# Chronos.net
KiCad netlist of a schematic drawn in EAGLE
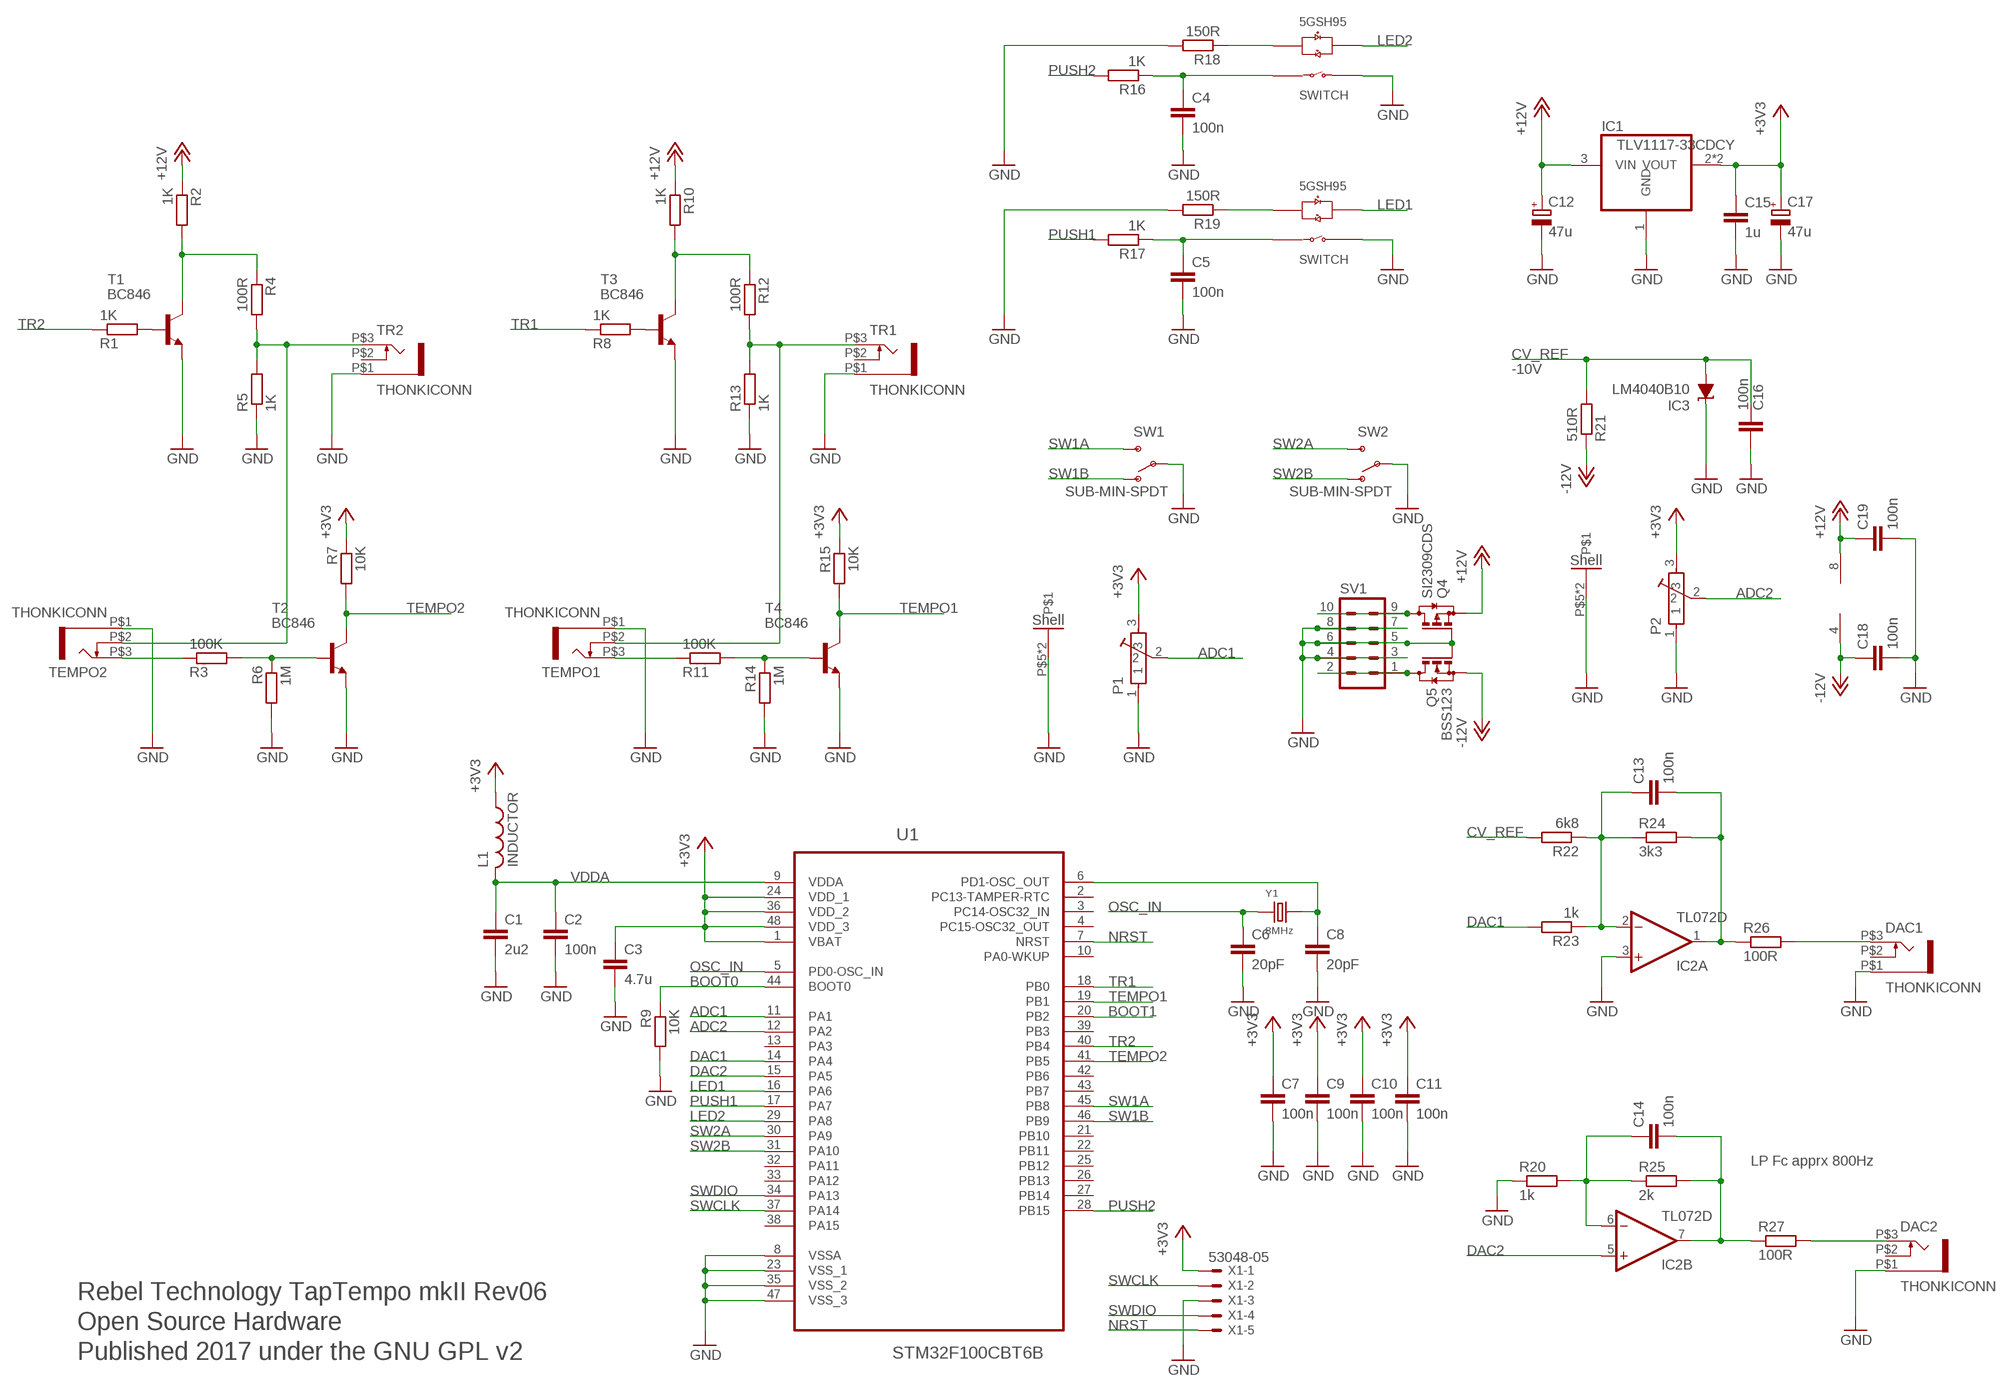
[diagram p0: schematic, sheet 1]

(export (version "E")
  (design (tool "Eeschema 10.0.6"))
  (components
    (comp (ref "C1")
      (value "2u2")
      (footprint "eagle-import:C0603")
      (libsource (lib "eagle-import") (part "C-EUC0603"))
    )
    (comp (ref "C2")
      (value "100n")
      (footprint "eagle-import:C0603")
      (libsource (lib "eagle-import") (part "C-EUC0603"))
    )
    (comp (ref "C3")
      (value "4.7u")
      (footprint "eagle-import:C0603")
      (libsource (lib "eagle-import") (part "C-EUC0603"))
    )
    (comp (ref "C4")
      (value "100n")
      (footprint "eagle-import:C0603")
      (libsource (lib "eagle-import") (part "C-EUC0603"))
    )
    (comp (ref "C5")
      (value "100n")
      (footprint "eagle-import:C0603")
      (libsource (lib "eagle-import") (part "C-EUC0603"))
    )
    (comp (ref "C6")
      (value "20pF")
      (footprint "eagle-import:C0603")
      (libsource (lib "eagle-import") (part "C-EUC0603"))
    )
    (comp (ref "C7")
      (value "100n")
      (footprint "eagle-import:C0603")
      (libsource (lib "eagle-import") (part "C-EUC0603"))
    )
    (comp (ref "C8")
      (value "20pF")
      (footprint "eagle-import:C0603")
      (libsource (lib "eagle-import") (part "C-EUC0603"))
    )
    (comp (ref "C9")
      (value "100n")
      (footprint "eagle-import:C0603")
      (libsource (lib "eagle-import") (part "C-EUC0603"))
    )
    (comp (ref "C10")
      (value "100n")
      (footprint "eagle-import:C0603")
      (libsource (lib "eagle-import") (part "C-EUC0603"))
    )
    (comp (ref "C11")
      (value "100n")
      (footprint "eagle-import:C0603")
      (libsource (lib "eagle-import") (part "C-EUC0603"))
    )
    (comp (ref "C12")
      (value "47u")
      (footprint "eagle-import:CPOL-5")
      (libsource (lib "eagle-import") (part "CPOL-EU153CLV-0505"))
    )
    (comp (ref "C13")
      (value "100n")
      (footprint "eagle-import:C0603")
      (libsource (lib "eagle-import") (part "C-EUC0603"))
    )
    (comp (ref "C14")
      (value "100n")
      (footprint "eagle-import:C0603")
      (libsource (lib "eagle-import") (part "C-EUC0603"))
    )
    (comp (ref "C15")
      (value "1u")
      (footprint "eagle-import:C0603")
      (libsource (lib "eagle-import") (part "C-EUC0603"))
    )
    (comp (ref "C16")
      (value "100n")
      (footprint "eagle-import:C0603")
      (libsource (lib "eagle-import") (part "C-EUC0603"))
    )
    (comp (ref "C17")
      (value "47u")
      (footprint "eagle-import:CPOL-5")
      (libsource (lib "eagle-import") (part "CPOL-EU153CLV-0505"))
    )
    (comp (ref "C18")
      (value "100n")
      (footprint "eagle-import:C0603")
      (libsource (lib "eagle-import") (part "C-EUC0603"))
    )
    (comp (ref "C19")
      (value "100n")
      (footprint "eagle-import:C0603")
      (libsource (lib "eagle-import") (part "C-EUC0603"))
    )
    (comp (ref "DAC1")
      (value "THONKICONN")
      (footprint "eagle-import:THONKICONN")
      (libsource (lib "eagle-import") (part "THONKICONN"))
    )
    (comp (ref "DAC2")
      (value "THONKICONN")
      (footprint "eagle-import:THONKICONN")
      (libsource (lib "eagle-import") (part "THONKICONN"))
    )
    (comp (ref "IC1")
      (value "TLV1117-33CDCY")
      (footprint "eagle-import:SOT223")
      (fields (field (name "MPN") "REG1117"))
      (libsource (lib "eagle-import") (part "REG1117"))
    )
    (comp (ref "IC2")
      (value "TL072D")
      (footprint "eagle-import:SO08")
      (libsource (lib "eagle-import") (part "TL072D"))
    )
    (comp (ref "IC3")
      (value "LM4040B10")
      (footprint "eagle-import:DBZ_R-PDSO-G3")
      (fields (field (name "MF") "TEXAS INSTRUMENT CONNECTORS") (field (name "MPN") "LM4041C12QDBZT"))
      (libsource (lib "eagle-import") (part "LM4041DBZC12"))
    )
    (comp (ref "L1")
      (value "INDUCTOR")
      (footprint "eagle-import:0603")
      (libsource (lib "eagle-import") (part "INDUCTOR"))
    )
    (comp (ref "P1")
      (value "POT-ALPS-RK09L1140")
      (footprint "eagle-import:POT-ALPS-RK09L1140")
      (libsource (lib "eagle-import") (part "POT-ALPS-RK09L1140"))
    )
    (comp (ref "P2")
      (value "POT-ALPS-RK09L1140")
      (footprint "eagle-import:POT-ALPS-RK09L1140")
      (libsource (lib "eagle-import") (part "POT-ALPS-RK09L1140"))
    )
    (comp (ref "PUSH1")
      (value "5GTH9")
      (footprint "eagle-import:5GTH9")
      (libsource (lib "eagle-import") (part "5GTH9"))
    )
    (comp (ref "PUSH2")
      (value "5GTH9")
      (footprint "eagle-import:5GTH9")
      (libsource (lib "eagle-import") (part "5GTH9"))
    )
    (comp (ref "Q4")
      (value "SI2309CDS")
      (footprint "eagle-import:SOT23")
      (libsource (lib "eagle-import") (part "BSS84"))
    )
    (comp (ref "Q5")
      (value "BSS123")
      (footprint "eagle-import:SOT23")
      (libsource (lib "eagle-import") (part "BSS123"))
    )
    (comp (ref "R1")
      (value "1K")
      (footprint "eagle-import:0603")
      (libsource (lib "eagle-import") (part "R-EU_0603"))
    )
    (comp (ref "R2")
      (value "1K")
      (footprint "eagle-import:0603")
      (libsource (lib "eagle-import") (part "R-EU_0603"))
    )
    (comp (ref "R3")
      (value "100K")
      (footprint "eagle-import:0603")
      (libsource (lib "eagle-import") (part "R-EU_0603"))
    )
    (comp (ref "R4")
      (value "100R")
      (footprint "eagle-import:0603")
      (libsource (lib "eagle-import") (part "R-EU_0603"))
    )
    (comp (ref "R5")
      (value "1K")
      (footprint "eagle-import:0603")
      (libsource (lib "eagle-import") (part "R-EU_0603"))
    )
    (comp (ref "R6")
      (value "1M")
      (footprint "eagle-import:0603")
      (libsource (lib "eagle-import") (part "R-EU_0603"))
    )
    (comp (ref "R7")
      (value "10K")
      (footprint "eagle-import:0603")
      (libsource (lib "eagle-import") (part "R-EU_0603"))
    )
    (comp (ref "R8")
      (value "1K")
      (footprint "eagle-import:0603")
      (libsource (lib "eagle-import") (part "R-EU_0603"))
    )
    (comp (ref "R9")
      (value "10K")
      (footprint "eagle-import:0603")
      (libsource (lib "eagle-import") (part "R-EU_0603"))
    )
    (comp (ref "R10")
      (value "1K")
      (footprint "eagle-import:0603")
      (libsource (lib "eagle-import") (part "R-EU_0603"))
    )
    (comp (ref "R11")
      (value "100K")
      (footprint "eagle-import:0603")
      (libsource (lib "eagle-import") (part "R-EU_0603"))
    )
    (comp (ref "R12")
      (value "100R")
      (footprint "eagle-import:0603")
      (libsource (lib "eagle-import") (part "R-EU_0603"))
    )
    (comp (ref "R13")
      (value "1K")
      (footprint "eagle-import:0603")
      (libsource (lib "eagle-import") (part "R-EU_0603"))
    )
    (comp (ref "R14")
      (value "1M")
      (footprint "eagle-import:0603")
      (libsource (lib "eagle-import") (part "R-EU_0603"))
    )
    (comp (ref "R15")
      (value "10K")
      (footprint "eagle-import:0603")
      (libsource (lib "eagle-import") (part "R-EU_0603"))
    )
    (comp (ref "R16")
      (value "1K")
      (footprint "eagle-import:0603")
      (libsource (lib "eagle-import") (part "R-EU_0603"))
    )
    (comp (ref "R17")
      (value "1K")
      (footprint "eagle-import:0603")
      (libsource (lib "eagle-import") (part "R-EU_0603"))
    )
    (comp (ref "R18")
      (value "150R")
      (footprint "eagle-import:0603")
      (libsource (lib "eagle-import") (part "R-EU_0603"))
    )
    (comp (ref "R19")
      (value "150R")
      (footprint "eagle-import:0603")
      (libsource (lib "eagle-import") (part "R-EU_0603"))
    )
    (comp (ref "R20")
      (value "1k")
      (footprint "eagle-import:0603")
      (libsource (lib "eagle-import") (part "R-EU_0603"))
    )
    (comp (ref "R21")
      (value "510R")
      (footprint "eagle-import:0603")
      (libsource (lib "eagle-import") (part "R-EU_0603"))
    )
    (comp (ref "R22")
      (value "6k8")
      (footprint "eagle-import:0603")
      (libsource (lib "eagle-import") (part "R-EU_0603"))
    )
    (comp (ref "R23")
      (value "1k")
      (footprint "eagle-import:0603")
      (libsource (lib "eagle-import") (part "R-EU_0603"))
    )
    (comp (ref "R24")
      (value "3k3")
      (footprint "eagle-import:0603")
      (libsource (lib "eagle-import") (part "R-EU_0603"))
    )
    (comp (ref "R25")
      (value "2k")
      (footprint "eagle-import:0603")
      (libsource (lib "eagle-import") (part "R-EU_0603"))
    )
    (comp (ref "R26")
      (value "100R")
      (footprint "eagle-import:0603")
      (libsource (lib "eagle-import") (part "R-EU_0603"))
    )
    (comp (ref "R27")
      (value "100R")
      (footprint "eagle-import:0603")
      (libsource (lib "eagle-import") (part "R-EU_0603"))
    )
    (comp (ref "SV1")
      (value "MA05-2")
      (footprint "eagle-import:MA05-2")
      (libsource (lib "eagle-import") (part "MA05-2"))
    )
    (comp (ref "SW1")
      (value "SUB-MIN-SPDT")
      (footprint "eagle-import:SUB-MIN-SPDT")
      (libsource (lib "eagle-import") (part "SUB-MIN-SPDT"))
    )
    (comp (ref "SW2")
      (value "SUB-MIN-SPDT")
      (footprint "eagle-import:SUB-MIN-SPDT")
      (libsource (lib "eagle-import") (part "SUB-MIN-SPDT"))
    )
    (comp (ref "T1")
      (value "BC846")
      (footprint "eagle-import:SOT23")
      (libsource (lib "eagle-import") (part "BC846"))
    )
    (comp (ref "T2")
      (value "BC846")
      (footprint "eagle-import:SOT23")
      (libsource (lib "eagle-import") (part "BC846"))
    )
    (comp (ref "T3")
      (value "BC846")
      (footprint "eagle-import:SOT23")
      (libsource (lib "eagle-import") (part "BC846"))
    )
    (comp (ref "T4")
      (value "BC846")
      (footprint "eagle-import:SOT23")
      (libsource (lib "eagle-import") (part "BC846"))
    )
    (comp (ref "TEMPO1")
      (value "THONKICONN")
      (footprint "eagle-import:THONKICONN")
      (libsource (lib "eagle-import") (part "THONKICONN"))
    )
    (comp (ref "TEMPO2")
      (value "THONKICONN")
      (footprint "eagle-import:THONKICONN")
      (libsource (lib "eagle-import") (part "THONKICONN"))
    )
    (comp (ref "TR1")
      (value "THONKICONN")
      (footprint "eagle-import:THONKICONN")
      (libsource (lib "eagle-import") (part "THONKICONN"))
    )
    (comp (ref "TR2")
      (value "THONKICONN")
      (footprint "eagle-import:THONKICONN")
      (libsource (lib "eagle-import") (part "THONKICONN"))
    )
    (comp (ref "U1")
      (value "STM32F100CBT6B")
      (footprint "eagle-import:QFP50P900X900X160-48N")
      (libsource (lib "eagle-import") (part "STM32F100CBT6B"))
    )
    (comp (ref "X1")
      (value "53048-05")
      (footprint "eagle-import:53048-05")
      (fields (field (name "MF") "MOLEX") (field (name "MPN") "53048-0510"))
      (libsource (lib "eagle-import") (part "53?-05048"))
    )
    (comp (ref "Y1")
      (value "8MHz")
      (footprint "eagle-import:X2-SMD-5.0X3.2X1.3MM")
      (fields (field (name "MPN") "5032/2P"))
      (libsource (lib "eagle-import") (part "SMD-CRYSTAL-8MHZ-20PF-20PPM(2P-5.0X3.2MM)"))
    )
  )
  (nets
    (net (code "1") (name "+3V3") (class "Default")
      (node (ref "C10") (pin "1") (pinfunction "1_1") (pintype "passive"))
      (node (ref "C11") (pin "1") (pinfunction "1_1") (pintype "passive"))
      (node (ref "C15") (pin "1") (pinfunction "1_1") (pintype "passive"))
      (node (ref "C17") (pin "+") (pinfunction "+_+") (pintype "passive"))
      (node (ref "C3") (pin "1") (pinfunction "1_1") (pintype "passive"))
      (node (ref "C7") (pin "1") (pinfunction "1_1") (pintype "passive"))
      (node (ref "C9") (pin "1") (pinfunction "1_1") (pintype "passive"))
      (node (ref "IC1") (pin "2") (pinfunction "VOUT_2") (pintype "output"))
      (node (ref "IC1") (pin "4") (pinfunction "VOUT_4") (pintype "output"))
      (node (ref "L1") (pin "1") (pinfunction "1_1") (pintype "passive"))
      (node (ref "P1") (pin "3") (pinfunction "3_3") (pintype "bidirectional"))
      (node (ref "P2") (pin "3") (pinfunction "3_3") (pintype "bidirectional"))
      (node (ref "R15") (pin "1") (pinfunction "1_1") (pintype "passive"))
      (node (ref "R7") (pin "1") (pinfunction "1_1") (pintype "passive"))
      (node (ref "U1") (pin "1") (pinfunction "VBAT_1") (pintype "power_in"))
      (node (ref "U1") (pin "24") (pinfunction "VDD_1_24") (pintype "power_in"))
      (node (ref "U1") (pin "36") (pinfunction "VDD_2_36") (pintype "power_in"))
      (node (ref "U1") (pin "48") (pinfunction "VDD_3_48") (pintype "power_in"))
      (node (ref "X1") (pin "1") (pinfunction "S_1") (pintype "passive"))
    )
    (net (code "2") (name "+12V") (class "Default")
      (node (ref "C12") (pin "+") (pinfunction "+_+") (pintype "passive"))
      (node (ref "C19") (pin "1") (pinfunction "1_1") (pintype "passive"))
      (node (ref "IC1") (pin "3") (pinfunction "VIN_3") (pintype "input"))
      (node (ref "IC2") (pin "8") (pinfunction "V+_8") (pintype "power_in"))
      (node (ref "Q4") (pin "2") (pinfunction "S_2") (pintype "passive"))
      (node (ref "R10") (pin "1") (pinfunction "1_1") (pintype "passive"))
      (node (ref "R2") (pin "1") (pinfunction "1_1") (pintype "passive"))
    )
    (net (code "3") (name "-12V") (class "Default")
      (node (ref "C18") (pin "1") (pinfunction "1_1") (pintype "passive"))
      (node (ref "IC2") (pin "4") (pinfunction "V-_4") (pintype "power_in"))
      (node (ref "Q5") (pin "2") (pinfunction "S_2") (pintype "passive"))
      (node (ref "R21") (pin "1") (pinfunction "1_1") (pintype "passive"))
    )
    (net (code "4") (name "/ADC1") (class "Default")
      (node (ref "P1") (pin "2") (pinfunction "2_2") (pintype "bidirectional"))
      (node (ref "U1") (pin "11") (pinfunction "PA1_11") (pintype "bidirectional"))
    )
    (net (code "5") (name "/ADC2") (class "Default")
      (node (ref "P2") (pin "2") (pinfunction "2_2") (pintype "bidirectional"))
      (node (ref "U1") (pin "12") (pinfunction "PA2_12") (pintype "bidirectional"))
    )
    (net (code "6") (name "/BOOT0") (class "Default")
      (node (ref "R9") (pin "1") (pinfunction "1_1") (pintype "passive"))
      (node (ref "U1") (pin "44") (pinfunction "BOOT0_44") (pintype "input"))
    )
    (net (code "7") (name "/BOOT1") (class "Default")
      (node (ref "U1") (pin "20") (pinfunction "PB2_20") (pintype "bidirectional"))
    )
    (net (code "8") (name "/CV_REF") (class "Default")
      (node (ref "C16") (pin "1") (pinfunction "1_1") (pintype "passive"))
      (node (ref "IC3") (pin "2") (pinfunction "A_2") (pintype "passive"))
      (node (ref "R21") (pin "2") (pinfunction "2_2") (pintype "passive"))
      (node (ref "R22") (pin "2") (pinfunction "2_2") (pintype "passive"))
    )
    (net (code "9") (name "/DAC1") (class "Default")
      (node (ref "R23") (pin "2") (pinfunction "2_2") (pintype "passive"))
      (node (ref "U1") (pin "14") (pinfunction "PA4_14") (pintype "bidirectional"))
    )
    (net (code "10") (name "/DAC2") (class "Default")
      (node (ref "IC2") (pin "5") (pinfunction "+IN_5") (pintype "input"))
      (node (ref "U1") (pin "15") (pinfunction "PA5_15") (pintype "bidirectional"))
    )
    (net (code "11") (name "/LED1") (class "Default")
      (node (ref "PUSH1") (pin "+3") (pinfunction "LED_R+_+3") (pintype "bidirectional"))
      (node (ref "U1") (pin "16") (pinfunction "PA6_16") (pintype "bidirectional"))
    )
    (net (code "12") (name "/LED2") (class "Default")
      (node (ref "PUSH2") (pin "+3") (pinfunction "LED_R+_+3") (pintype "bidirectional"))
      (node (ref "U1") (pin "29") (pinfunction "PA8_29") (pintype "bidirectional"))
    )
    (net (code "13") (name "/NRST") (class "Default")
      (node (ref "U1") (pin "7") (pinfunction "NRST_7") (pintype "bidirectional"))
      (node (ref "X1") (pin "5") (pinfunction "S_5") (pintype "passive"))
    )
    (net (code "14") (name "/OSC_IN") (class "Default")
      (node (ref "C6") (pin "1") (pinfunction "1_1") (pintype "passive"))
      (node (ref "U1") (pin "5") (pinfunction "PD0-OSC_IN_5") (pintype "input"))
      (node (ref "Y1") (pin "1") (pinfunction "1_1") (pintype "passive"))
    )
    (net (code "15") (name "/PUSH1") (class "Default")
      (node (ref "R17") (pin "2") (pinfunction "2_2") (pintype "passive"))
      (node (ref "U1") (pin "17") (pinfunction "PA7_17") (pintype "bidirectional"))
    )
    (net (code "16") (name "/PUSH2") (class "Default")
      (node (ref "R16") (pin "2") (pinfunction "2_2") (pintype "passive"))
      (node (ref "U1") (pin "28") (pinfunction "PB15_28") (pintype "bidirectional"))
    )
    (net (code "17") (name "/SW1A") (class "Default")
      (node (ref "SW1") (pin "3") (pinfunction "S_3") (pintype "passive"))
      (node (ref "U1") (pin "45") (pinfunction "PB8_45") (pintype "bidirectional"))
    )
    (net (code "18") (name "/SW1B") (class "Default")
      (node (ref "SW1") (pin "1") (pinfunction "O_1") (pintype "passive"))
      (node (ref "U1") (pin "46") (pinfunction "PB9_46") (pintype "bidirectional"))
    )
    (net (code "19") (name "/SW2A") (class "Default")
      (node (ref "SW2") (pin "3") (pinfunction "S_3") (pintype "passive"))
      (node (ref "U1") (pin "30") (pinfunction "PA9_30") (pintype "bidirectional"))
    )
    (net (code "20") (name "/SW2B") (class "Default")
      (node (ref "SW2") (pin "1") (pinfunction "O_1") (pintype "passive"))
      (node (ref "U1") (pin "31") (pinfunction "PA10_31") (pintype "bidirectional"))
    )
    (net (code "21") (name "/SWCLK") (class "Default")
      (node (ref "U1") (pin "37") (pinfunction "PA14_37") (pintype "bidirectional"))
      (node (ref "X1") (pin "2") (pinfunction "S_2") (pintype "passive"))
    )
    (net (code "22") (name "/SWDIO") (class "Default")
      (node (ref "U1") (pin "34") (pinfunction "PA13_34") (pintype "bidirectional"))
      (node (ref "X1") (pin "4") (pinfunction "S_4") (pintype "passive"))
    )
    (net (code "23") (name "/TEMPO1") (class "Default")
      (node (ref "R15") (pin "2") (pinfunction "2_2") (pintype "passive"))
      (node (ref "T4") (pin "3") (pinfunction "C_3") (pintype "passive"))
      (node (ref "U1") (pin "19") (pinfunction "PB1_19") (pintype "bidirectional"))
    )
    (net (code "24") (name "/TEMPO2") (class "Default")
      (node (ref "R7") (pin "2") (pinfunction "2_2") (pintype "passive"))
      (node (ref "T2") (pin "3") (pinfunction "C_3") (pintype "passive"))
      (node (ref "U1") (pin "41") (pinfunction "PB5_41") (pintype "bidirectional"))
    )
    (net (code "25") (name "/TR1") (class "Default")
      (node (ref "R8") (pin "1") (pinfunction "1_1") (pintype "passive"))
      (node (ref "U1") (pin "18") (pinfunction "PB0_18") (pintype "bidirectional"))
    )
    (net (code "26") (name "/TR2") (class "Default")
      (node (ref "R1") (pin "1") (pinfunction "1_1") (pintype "passive"))
      (node (ref "U1") (pin "40") (pinfunction "PB4_40") (pintype "bidirectional"))
    )
    (net (code "27") (name "/VDDA") (class "Default")
      (node (ref "C1") (pin "1") (pinfunction "1_1") (pintype "passive"))
      (node (ref "C2") (pin "1") (pinfunction "1_1") (pintype "passive"))
      (node (ref "L1") (pin "2") (pinfunction "2_2") (pintype "passive"))
      (node (ref "U1") (pin "9") (pinfunction "VDDA_9") (pintype "power_in"))
    )
    (net (code "28") (name "GND") (class "Default")
      (node (ref "C1") (pin "2") (pinfunction "2_2") (pintype "passive"))
      (node (ref "C10") (pin "2") (pinfunction "2_2") (pintype "passive"))
      (node (ref "C11") (pin "2") (pinfunction "2_2") (pintype "passive"))
      (node (ref "C12") (pin "-") (pinfunction "-_-") (pintype "passive"))
      (node (ref "C15") (pin "2") (pinfunction "2_2") (pintype "passive"))
      (node (ref "C16") (pin "2") (pinfunction "2_2") (pintype "passive"))
      (node (ref "C17") (pin "-") (pinfunction "-_-") (pintype "passive"))
      (node (ref "C18") (pin "2") (pinfunction "2_2") (pintype "passive"))
      (node (ref "C19") (pin "2") (pinfunction "2_2") (pintype "passive"))
      (node (ref "C2") (pin "2") (pinfunction "2_2") (pintype "passive"))
      (node (ref "C3") (pin "2") (pinfunction "2_2") (pintype "passive"))
      (node (ref "C4") (pin "2") (pinfunction "2_2") (pintype "passive"))
      (node (ref "C5") (pin "2") (pinfunction "2_2") (pintype "passive"))
      (node (ref "C6") (pin "2") (pinfunction "2_2") (pintype "passive"))
      (node (ref "C7") (pin "2") (pinfunction "2_2") (pintype "passive"))
      (node (ref "C8") (pin "2") (pinfunction "2_2") (pintype "passive"))
      (node (ref "C9") (pin "2") (pinfunction "2_2") (pintype "passive"))
      (node (ref "DAC1") (pin "P$1") (pinfunction "5_P$1") (pintype "passive"))
      (node (ref "DAC2") (pin "P$1") (pinfunction "5_P$1") (pintype "passive"))
      (node (ref "IC1") (pin "1") (pinfunction "GND_1") (pintype "power_in"))
      (node (ref "IC2") (pin "3") (pinfunction "+IN_3") (pintype "input"))
      (node (ref "IC3") (pin "1") (pinfunction "C_1") (pintype "passive"))
      (node (ref "P1") (pin "1") (pinfunction "1_1") (pintype "bidirectional"))
      (node (ref "P1") (pin "P$5") (pinfunction "P$1_P$5") (pintype "bidirectional"))
      (node (ref "P1") (pin "P$6") (pinfunction "P$1_P$6") (pintype "bidirectional"))
      (node (ref "P2") (pin "1") (pinfunction "1_1") (pintype "bidirectional"))
      (node (ref "P2") (pin "P$5") (pinfunction "P$1_P$5") (pintype "bidirectional"))
      (node (ref "P2") (pin "P$6") (pinfunction "P$1_P$6") (pintype "bidirectional"))
      (node (ref "PUSH1") (pin "1") (pinfunction "SWITCH_B_1") (pintype "bidirectional"))
      (node (ref "PUSH2") (pin "1") (pinfunction "SWITCH_B_1") (pintype "bidirectional"))
      (node (ref "Q4") (pin "1") (pinfunction "G_1") (pintype "passive"))
      (node (ref "Q5") (pin "1") (pinfunction "G_1") (pintype "passive"))
      (node (ref "R13") (pin "1") (pinfunction "1_1") (pintype "passive"))
      (node (ref "R14") (pin "2") (pinfunction "2_2") (pintype "passive"))
      (node (ref "R18") (pin "2") (pinfunction "2_2") (pintype "passive"))
      (node (ref "R19") (pin "2") (pinfunction "2_2") (pintype "passive"))
      (node (ref "R20") (pin "1") (pinfunction "1_1") (pintype "passive"))
      (node (ref "R5") (pin "1") (pinfunction "1_1") (pintype "passive"))
      (node (ref "R6") (pin "2") (pinfunction "2_2") (pintype "passive"))
      (node (ref "R9") (pin "2") (pinfunction "2_2") (pintype "passive"))
      (node (ref "SV1") (pin "3") (pinfunction "3_3") (pintype "passive"))
      (node (ref "SV1") (pin "4") (pinfunction "4_4") (pintype "passive"))
      (node (ref "SV1") (pin "5") (pinfunction "5_5") (pintype "passive"))
      (node (ref "SV1") (pin "6") (pinfunction "6_6") (pintype "passive"))
      (node (ref "SV1") (pin "7") (pinfunction "7_7") (pintype "passive"))
      (node (ref "SV1") (pin "8") (pinfunction "8_8") (pintype "passive"))
      (node (ref "SW1") (pin "2") (pinfunction "P_2") (pintype "passive"))
      (node (ref "SW2") (pin "2") (pinfunction "P_2") (pintype "passive"))
      (node (ref "T1") (pin "2") (pinfunction "E_2") (pintype "passive"))
      (node (ref "T2") (pin "2") (pinfunction "E_2") (pintype "passive"))
      (node (ref "T3") (pin "2") (pinfunction "E_2") (pintype "passive"))
      (node (ref "T4") (pin "2") (pinfunction "E_2") (pintype "passive"))
      (node (ref "TEMPO1") (pin "P$1") (pinfunction "5_P$1") (pintype "passive"))
      (node (ref "TEMPO2") (pin "P$1") (pinfunction "5_P$1") (pintype "passive"))
      (node (ref "TR1") (pin "P$1") (pinfunction "5_P$1") (pintype "passive"))
      (node (ref "TR2") (pin "P$1") (pinfunction "5_P$1") (pintype "passive"))
      (node (ref "U1") (pin "23") (pinfunction "VSS_1_23") (pintype "power_in"))
      (node (ref "U1") (pin "35") (pinfunction "VSS_2_35") (pintype "power_in"))
      (node (ref "U1") (pin "47") (pinfunction "VSS_3_47") (pintype "power_in"))
      (node (ref "U1") (pin "8") (pinfunction "VSSA_8") (pintype "power_in"))
      (node (ref "X1") (pin "3") (pinfunction "S_3") (pintype "passive"))
    )
    (net (code "29") (name "Net-(DAC1-3)") (class "Default")
      (node (ref "DAC1") (pin "P$3") (pinfunction "3_P$3") (pintype "passive"))
      (node (ref "R26") (pin "2") (pinfunction "2_2") (pintype "passive"))
    )
    (net (code "30") (name "Net-(DAC2-3)") (class "Default")
      (node (ref "DAC2") (pin "P$3") (pinfunction "3_P$3") (pintype "passive"))
      (node (ref "R27") (pin "2") (pinfunction "2_2") (pintype "passive"))
    )
    (net (code "31") (name "Net-(IC2A--IN)") (class "Default")
      (node (ref "C13") (pin "1") (pinfunction "1_1") (pintype "passive"))
      (node (ref "IC2") (pin "2") (pinfunction "-IN_2") (pintype "input"))
      (node (ref "R22") (pin "1") (pinfunction "1_1") (pintype "passive"))
      (node (ref "R23") (pin "1") (pinfunction "1_1") (pintype "passive"))
      (node (ref "R24") (pin "1") (pinfunction "1_1") (pintype "passive"))
    )
    (net (code "32") (name "Net-(IC2A-OUT)") (class "Default")
      (node (ref "C13") (pin "2") (pinfunction "2_2") (pintype "passive"))
      (node (ref "IC2") (pin "1") (pinfunction "OUT_1") (pintype "output"))
      (node (ref "R24") (pin "2") (pinfunction "2_2") (pintype "passive"))
      (node (ref "R26") (pin "1") (pinfunction "1_1") (pintype "passive"))
    )
    (net (code "33") (name "Net-(IC2B--IN)") (class "Default")
      (node (ref "C14") (pin "1") (pinfunction "1_1") (pintype "passive"))
      (node (ref "IC2") (pin "6") (pinfunction "-IN_6") (pintype "input"))
      (node (ref "R20") (pin "2") (pinfunction "2_2") (pintype "passive"))
      (node (ref "R25") (pin "1") (pinfunction "1_1") (pintype "passive"))
    )
    (net (code "34") (name "Net-(IC2B-OUT)") (class "Default")
      (node (ref "C14") (pin "2") (pinfunction "2_2") (pintype "passive"))
      (node (ref "IC2") (pin "7") (pinfunction "OUT_7") (pintype "output"))
      (node (ref "R25") (pin "2") (pinfunction "2_2") (pintype "passive"))
      (node (ref "R27") (pin "1") (pinfunction "1_1") (pintype "passive"))
    )
    (net (code "35") (name "Net-(PUSH1-LED_G+)") (class "Default")
      (node (ref "PUSH1") (pin "-2") (pinfunction "LED_G+_-2") (pintype "bidirectional"))
      (node (ref "R19") (pin "1") (pinfunction "1_1") (pintype "passive"))
    )
    (net (code "36") (name "Net-(PUSH1-SWITCH_A)") (class "Default")
      (node (ref "C5") (pin "1") (pinfunction "1_1") (pintype "passive"))
      (node (ref "PUSH1") (pin "4") (pinfunction "SWITCH_A_4") (pintype "bidirectional"))
      (node (ref "R17") (pin "1") (pinfunction "1_1") (pintype "passive"))
    )
    (net (code "37") (name "Net-(PUSH2-LED_G+)") (class "Default")
      (node (ref "PUSH2") (pin "-2") (pinfunction "LED_G+_-2") (pintype "bidirectional"))
      (node (ref "R18") (pin "1") (pinfunction "1_1") (pintype "passive"))
    )
    (net (code "38") (name "Net-(PUSH2-SWITCH_A)") (class "Default")
      (node (ref "C4") (pin "1") (pinfunction "1_1") (pintype "passive"))
      (node (ref "PUSH2") (pin "4") (pinfunction "SWITCH_A_4") (pintype "bidirectional"))
      (node (ref "R16") (pin "1") (pinfunction "1_1") (pintype "passive"))
    )
    (net (code "39") (name "Net-(Q4-D)") (class "Default")
      (node (ref "Q4") (pin "3") (pinfunction "D_3") (pintype "passive"))
      (node (ref "SV1") (pin "10") (pinfunction "10_10") (pintype "passive"))
      (node (ref "SV1") (pin "9") (pinfunction "9_9") (pintype "passive"))
    )
    (net (code "40") (name "Net-(Q5-D)") (class "Default")
      (node (ref "Q5") (pin "3") (pinfunction "D_3") (pintype "passive"))
      (node (ref "SV1") (pin "1") (pinfunction "1_1") (pintype "passive"))
      (node (ref "SV1") (pin "2") (pinfunction "2_2") (pintype "passive"))
    )
    (net (code "41") (name "Net-(T1-B)") (class "Default")
      (node (ref "R1") (pin "2") (pinfunction "2_2") (pintype "passive"))
      (node (ref "T1") (pin "1") (pinfunction "B_1") (pintype "passive"))
    )
    (net (code "42") (name "Net-(T1-C)") (class "Default")
      (node (ref "R2") (pin "2") (pinfunction "2_2") (pintype "passive"))
      (node (ref "R4") (pin "1") (pinfunction "1_1") (pintype "passive"))
      (node (ref "T1") (pin "3") (pinfunction "C_3") (pintype "passive"))
    )
    (net (code "43") (name "Net-(T2-B)") (class "Default")
      (node (ref "R3") (pin "2") (pinfunction "2_2") (pintype "passive"))
      (node (ref "R6") (pin "1") (pinfunction "1_1") (pintype "passive"))
      (node (ref "T2") (pin "1") (pinfunction "B_1") (pintype "passive"))
    )
    (net (code "44") (name "Net-(T3-B)") (class "Default")
      (node (ref "R8") (pin "2") (pinfunction "2_2") (pintype "passive"))
      (node (ref "T3") (pin "1") (pinfunction "B_1") (pintype "passive"))
    )
    (net (code "45") (name "Net-(T3-C)") (class "Default")
      (node (ref "R10") (pin "2") (pinfunction "2_2") (pintype "passive"))
      (node (ref "R12") (pin "1") (pinfunction "1_1") (pintype "passive"))
      (node (ref "T3") (pin "3") (pinfunction "C_3") (pintype "passive"))
    )
    (net (code "46") (name "Net-(T4-B)") (class "Default")
      (node (ref "R11") (pin "2") (pinfunction "2_2") (pintype "passive"))
      (node (ref "R14") (pin "1") (pinfunction "1_1") (pintype "passive"))
      (node (ref "T4") (pin "1") (pinfunction "B_1") (pintype "passive"))
    )
    (net (code "47") (name "Net-(TEMPO1-3)") (class "Default")
      (node (ref "R11") (pin "1") (pinfunction "1_1") (pintype "passive"))
      (node (ref "TEMPO1") (pin "P$3") (pinfunction "3_P$3") (pintype "passive"))
    )
    (net (code "48") (name "Net-(TEMPO1-4)") (class "Default")
      (node (ref "R12") (pin "2") (pinfunction "2_2") (pintype "passive"))
      (node (ref "R13") (pin "2") (pinfunction "2_2") (pintype "passive"))
      (node (ref "TEMPO1") (pin "P$2") (pinfunction "4_P$2") (pintype "passive"))
      (node (ref "TR1") (pin "P$3") (pinfunction "3_P$3") (pintype "passive"))
    )
    (net (code "49") (name "Net-(TEMPO2-3)") (class "Default")
      (node (ref "R3") (pin "1") (pinfunction "1_1") (pintype "passive"))
      (node (ref "TEMPO2") (pin "P$3") (pinfunction "3_P$3") (pintype "passive"))
    )
    (net (code "50") (name "Net-(TEMPO2-4)") (class "Default")
      (node (ref "R4") (pin "2") (pinfunction "2_2") (pintype "passive"))
      (node (ref "R5") (pin "2") (pinfunction "2_2") (pintype "passive"))
      (node (ref "TEMPO2") (pin "P$2") (pinfunction "4_P$2") (pintype "passive"))
      (node (ref "TR2") (pin "P$3") (pinfunction "3_P$3") (pintype "passive"))
    )
    (net (code "51") (name "Net-(U1-PD1-OSC_OUT)") (class "Default")
      (node (ref "C8") (pin "1") (pinfunction "1_1") (pintype "passive"))
      (node (ref "U1") (pin "6") (pinfunction "PD1-OSC_OUT_6") (pintype "output"))
      (node (ref "Y1") (pin "2") (pinfunction "2_2") (pintype "passive"))
    )
    (net (code "52") (name "unconnected-(DAC1-4-PadP$2)") (class "Default")
      (node (ref "DAC1") (pin "P$2") (pinfunction "4_P$2") (pintype "passive"))
    )
    (net (code "53") (name "unconnected-(DAC2-4-PadP$2)") (class "Default")
      (node (ref "DAC2") (pin "P$2") (pinfunction "4_P$2") (pintype "passive"))
    )
    (net (code "54") (name "unconnected-(TR1-4-PadP$2)") (class "Default")
      (node (ref "TR1") (pin "P$2") (pinfunction "4_P$2") (pintype "passive"))
    )
    (net (code "55") (name "unconnected-(TR2-4-PadP$2)") (class "Default")
      (node (ref "TR2") (pin "P$2") (pinfunction "4_P$2") (pintype "passive"))
    )
    (net (code "56") (name "unconnected-(U1-PA0-WKUP-Pad10)") (class "Default")
      (node (ref "U1") (pin "10") (pinfunction "PA0-WKUP_10") (pintype "bidirectional"))
    )
    (net (code "57") (name "unconnected-(U1-PA3-Pad13)") (class "Default")
      (node (ref "U1") (pin "13") (pinfunction "PA3_13") (pintype "bidirectional"))
    )
    (net (code "58") (name "unconnected-(U1-PA11-Pad32)") (class "Default")
      (node (ref "U1") (pin "32") (pinfunction "PA11_32") (pintype "bidirectional"))
    )
    (net (code "59") (name "unconnected-(U1-PA12-Pad33)") (class "Default")
      (node (ref "U1") (pin "33") (pinfunction "PA12_33") (pintype "bidirectional"))
    )
    (net (code "60") (name "unconnected-(U1-PA15-Pad38)") (class "Default")
      (node (ref "U1") (pin "38") (pinfunction "PA15_38") (pintype "bidirectional"))
    )
    (net (code "61") (name "unconnected-(U1-PB3-Pad39)") (class "Default")
      (node (ref "U1") (pin "39") (pinfunction "PB3_39") (pintype "bidirectional"))
    )
    (net (code "62") (name "unconnected-(U1-PB6-Pad42)") (class "Default")
      (node (ref "U1") (pin "42") (pinfunction "PB6_42") (pintype "bidirectional"))
    )
    (net (code "63") (name "unconnected-(U1-PB7-Pad43)") (class "Default")
      (node (ref "U1") (pin "43") (pinfunction "PB7_43") (pintype "bidirectional"))
    )
    (net (code "64") (name "unconnected-(U1-PB10-Pad21)") (class "Default")
      (node (ref "U1") (pin "21") (pinfunction "PB10_21") (pintype "bidirectional"))
    )
    (net (code "65") (name "unconnected-(U1-PB11-Pad22)") (class "Default")
      (node (ref "U1") (pin "22") (pinfunction "PB11_22") (pintype "bidirectional"))
    )
    (net (code "66") (name "unconnected-(U1-PB12-Pad25)") (class "Default")
      (node (ref "U1") (pin "25") (pinfunction "PB12_25") (pintype "bidirectional"))
    )
    (net (code "67") (name "unconnected-(U1-PB13-Pad26)") (class "Default")
      (node (ref "U1") (pin "26") (pinfunction "PB13_26") (pintype "bidirectional"))
    )
    (net (code "68") (name "unconnected-(U1-PB14-Pad27)") (class "Default")
      (node (ref "U1") (pin "27") (pinfunction "PB14_27") (pintype "bidirectional"))
    )
    (net (code "69") (name "unconnected-(U1-PC13-TAMPER-RTC-Pad2)") (class "Default")
      (node (ref "U1") (pin "2") (pinfunction "PC13-TAMPER-RTC_2") (pintype "bidirectional"))
    )
    (net (code "70") (name "unconnected-(U1-PC14-OSC32_IN-Pad3)") (class "Default")
      (node (ref "U1") (pin "3") (pinfunction "PC14-OSC32_IN_3") (pintype "bidirectional"))
    )
    (net (code "71") (name "unconnected-(U1-PC15-OSC32_OUT-Pad4)") (class "Default")
      (node (ref "U1") (pin "4") (pinfunction "PC15-OSC32_OUT_4") (pintype "bidirectional"))
    )
  )
)
